# wtv_sch.net
KiCad netlist of a schematic drawn in EAGLE
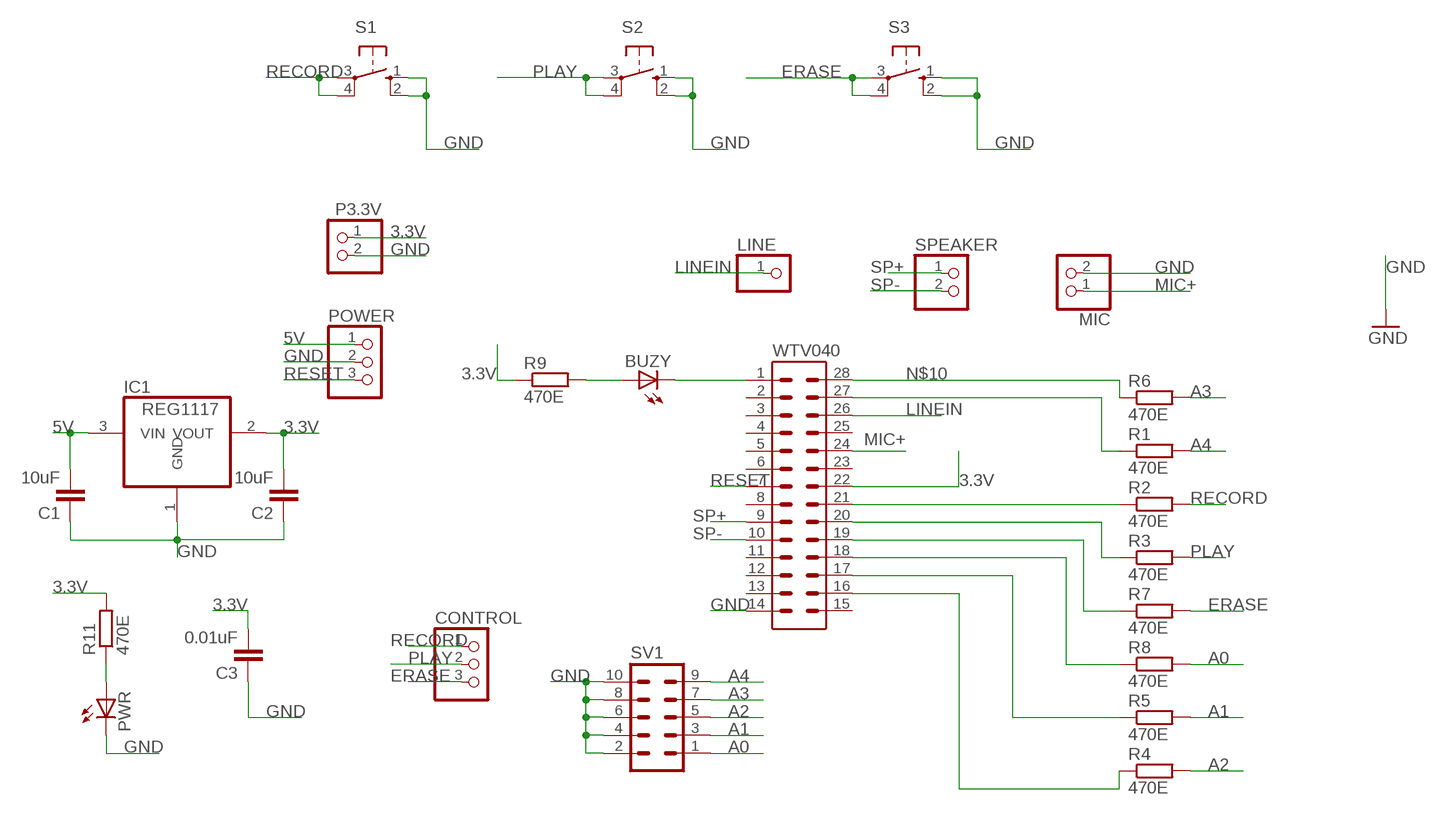
[diagram p0: schematic, sheet 1]

(export (version "E")
  (design (tool "Eeschema 10.0.6"))
  (components
    (comp (ref "BUZY")
      (value "LEDSML0805")
      (footprint "eagle-import:SML0805")
      (libsource (lib "eagle-import") (part "LEDSML0805"))
    )
    (comp (ref "C1")
      (value "10uF")
      (footprint "eagle-import:C0805")
      (libsource (lib "eagle-import") (part "C-EUC0805"))
    )
    (comp (ref "C2")
      (value "10uF")
      (footprint "eagle-import:C0805")
      (libsource (lib "eagle-import") (part "C-EUC0805"))
    )
    (comp (ref "C3")
      (value "0.01uF")
      (footprint "eagle-import:C0805")
      (libsource (lib "eagle-import") (part "C-EUC0805"))
    )
    (comp (ref "CONTROL")
      (value "PINHD-1X3")
      (footprint "eagle-import:1X03")
      (libsource (lib "eagle-import") (part "PINHD-1X3"))
    )
    (comp (ref "IC1")
      (value "REG1117")
      (footprint "eagle-import:SOT223")
      (libsource (lib "eagle-import") (part "REG1117"))
    )
    (comp (ref "LINE")
      (value "PINHD-1X1")
      (footprint "eagle-import:1X01")
      (libsource (lib "eagle-import") (part "PINHD-1X1"))
    )
    (comp (ref "MIC")
      (value "PINHD-1X2")
      (footprint "eagle-import:1X02")
      (libsource (lib "eagle-import") (part "PINHD-1X2"))
    )
    (comp (ref "P3.3V")
      (value "PINHD-1X2")
      (footprint "eagle-import:1X02")
      (libsource (lib "eagle-import") (part "PINHD-1X2"))
    )
    (comp (ref "POWER")
      (value "PINHD-1X3")
      (footprint "eagle-import:1X03")
      (libsource (lib "eagle-import") (part "PINHD-1X3"))
    )
    (comp (ref "PWR")
      (value "LEDSML0805")
      (footprint "eagle-import:SML0805")
      (libsource (lib "eagle-import") (part "LEDSML0805"))
    )
    (comp (ref "R1")
      (value "470E")
      (footprint "eagle-import:R0805")
      (libsource (lib "eagle-import") (part "R-EU_R0805"))
    )
    (comp (ref "R2")
      (value "470E")
      (footprint "eagle-import:R0805")
      (libsource (lib "eagle-import") (part "R-EU_R0805"))
    )
    (comp (ref "R3")
      (value "470E")
      (footprint "eagle-import:R0805")
      (libsource (lib "eagle-import") (part "R-EU_R0805"))
    )
    (comp (ref "R4")
      (value "470E")
      (footprint "eagle-import:R0805")
      (libsource (lib "eagle-import") (part "R-EU_R0805"))
    )
    (comp (ref "R5")
      (value "470E")
      (footprint "eagle-import:R0805")
      (libsource (lib "eagle-import") (part "R-EU_R0805"))
    )
    (comp (ref "R6")
      (value "470E")
      (footprint "eagle-import:R0805")
      (libsource (lib "eagle-import") (part "R-EU_R0805"))
    )
    (comp (ref "R7")
      (value "470E")
      (footprint "eagle-import:R0805")
      (libsource (lib "eagle-import") (part "R-EU_R0805"))
    )
    (comp (ref "R8")
      (value "470E")
      (footprint "eagle-import:R0805")
      (libsource (lib "eagle-import") (part "R-EU_R0805"))
    )
    (comp (ref "R9")
      (value "470E")
      (footprint "eagle-import:R0805")
      (libsource (lib "eagle-import") (part "R-EU_R0805"))
    )
    (comp (ref "R11")
      (value "470E")
      (footprint "eagle-import:R0805")
      (libsource (lib "eagle-import") (part "R-EU_R0805"))
    )
    (comp (ref "S1")
      (value "10-XX")
      (footprint "eagle-import:B3F-10XX")
      (fields (field (name "MPN") "B3F-1000"))
      (libsource (lib "eagle-import") (part "10-XX"))
    )
    (comp (ref "S2")
      (value "10-XX")
      (footprint "eagle-import:B3F-10XX")
      (fields (field (name "MPN") "B3F-1000"))
      (libsource (lib "eagle-import") (part "10-XX"))
    )
    (comp (ref "S3")
      (value "10-XX")
      (footprint "eagle-import:B3F-10XX")
      (fields (field (name "MPN") "B3F-1000"))
      (libsource (lib "eagle-import") (part "10-XX"))
    )
    (comp (ref "SPEAKER")
      (value "PINHD-1X2")
      (footprint "eagle-import:1X02")
      (libsource (lib "eagle-import") (part "PINHD-1X2"))
    )
    (comp (ref "SV1")
      (value "MA05-2")
      (footprint "eagle-import:MA05-2")
      (libsource (lib "eagle-import") (part "MA05-2"))
    )
    (comp (ref "WTV040")
      (value "IC28P")
      (footprint "eagle-import:IC28P")
      (libsource (lib "eagle-import") (part "IC28P"))
    )
  )
  (nets
    (net (code "1") (name "/3.3V") (class "Default")
      (node (ref "C2") (pin "2") (pinfunction "2_2") (pintype "passive"))
      (node (ref "C3") (pin "2") (pinfunction "2_2") (pintype "passive"))
      (node (ref "IC1") (pin "2") (pinfunction "VOUT_2") (pintype "output"))
      (node (ref "P3.3V") (pin "1") (pinfunction "1_1") (pintype "passive"))
      (node (ref "R11") (pin "2") (pinfunction "2_2") (pintype "passive"))
      (node (ref "R9") (pin "1") (pinfunction "1_1") (pintype "passive"))
      (node (ref "WTV040") (pin "22") (pinfunction "22_22") (pintype "passive"))
    )
    (net (code "2") (name "/5V") (class "Default")
      (node (ref "C1") (pin "2") (pinfunction "2_2") (pintype "passive"))
      (node (ref "IC1") (pin "3") (pinfunction "VIN_3") (pintype "input"))
      (node (ref "POWER") (pin "1") (pinfunction "1_1") (pintype "passive"))
    )
    (net (code "3") (name "/A0") (class "Default")
      (node (ref "R8") (pin "2") (pinfunction "2_2") (pintype "passive"))
      (node (ref "SV1") (pin "1") (pinfunction "1_1") (pintype "passive"))
    )
    (net (code "4") (name "/A1") (class "Default")
      (node (ref "R5") (pin "2") (pinfunction "2_2") (pintype "passive"))
      (node (ref "SV1") (pin "3") (pinfunction "3_3") (pintype "passive"))
    )
    (net (code "5") (name "/A2") (class "Default")
      (node (ref "R4") (pin "2") (pinfunction "2_2") (pintype "passive"))
      (node (ref "SV1") (pin "5") (pinfunction "5_5") (pintype "passive"))
    )
    (net (code "6") (name "/A3") (class "Default")
      (node (ref "R6") (pin "2") (pinfunction "2_2") (pintype "passive"))
      (node (ref "SV1") (pin "7") (pinfunction "7_7") (pintype "passive"))
    )
    (net (code "7") (name "/A4") (class "Default")
      (node (ref "R1") (pin "2") (pinfunction "2_2") (pintype "passive"))
      (node (ref "SV1") (pin "9") (pinfunction "9_9") (pintype "passive"))
    )
    (net (code "8") (name "/ERASE") (class "Default")
      (node (ref "CONTROL") (pin "3") (pinfunction "3_3") (pintype "passive"))
      (node (ref "R7") (pin "2") (pinfunction "2_2") (pintype "passive"))
      (node (ref "S3") (pin "3") (pinfunction "P_3") (pintype "passive"))
      (node (ref "S3") (pin "4") (pinfunction "P1_4") (pintype "passive"))
    )
    (net (code "9") (name "/LINEIN") (class "Default")
      (node (ref "LINE") (pin "1") (pinfunction "1_1") (pintype "passive"))
      (node (ref "WTV040") (pin "26") (pinfunction "26_26") (pintype "passive"))
    )
    (net (code "10") (name "/MIC+") (class "Default")
      (node (ref "MIC") (pin "1") (pinfunction "1_1") (pintype "passive"))
      (node (ref "WTV040") (pin "24") (pinfunction "24_24") (pintype "passive"))
    )
    (net (code "11") (name "/N$10") (class "Default")
      (node (ref "R6") (pin "1") (pinfunction "1_1") (pintype "passive"))
      (node (ref "WTV040") (pin "28") (pinfunction "28_28") (pintype "passive"))
    )
    (net (code "12") (name "/PLAY") (class "Default")
      (node (ref "CONTROL") (pin "2") (pinfunction "2_2") (pintype "passive"))
      (node (ref "R3") (pin "2") (pinfunction "2_2") (pintype "passive"))
      (node (ref "S2") (pin "3") (pinfunction "P_3") (pintype "passive"))
      (node (ref "S2") (pin "4") (pinfunction "P1_4") (pintype "passive"))
    )
    (net (code "13") (name "/RECORD") (class "Default")
      (node (ref "CONTROL") (pin "1") (pinfunction "1_1") (pintype "passive"))
      (node (ref "R2") (pin "2") (pinfunction "2_2") (pintype "passive"))
      (node (ref "S1") (pin "3") (pinfunction "P_3") (pintype "passive"))
      (node (ref "S1") (pin "4") (pinfunction "P1_4") (pintype "passive"))
    )
    (net (code "14") (name "/RESET") (class "Default")
      (node (ref "POWER") (pin "3") (pinfunction "3_3") (pintype "passive"))
      (node (ref "WTV040") (pin "7") (pinfunction "7_7") (pintype "passive"))
    )
    (net (code "15") (name "/SP+") (class "Default")
      (node (ref "SPEAKER") (pin "1") (pinfunction "1_1") (pintype "passive"))
      (node (ref "WTV040") (pin "9") (pinfunction "9_9") (pintype "passive"))
    )
    (net (code "16") (name "/SP-") (class "Default")
      (node (ref "SPEAKER") (pin "2") (pinfunction "2_2") (pintype "passive"))
      (node (ref "WTV040") (pin "10") (pinfunction "10_10") (pintype "passive"))
    )
    (net (code "17") (name "GND") (class "Default")
      (node (ref "C1") (pin "1") (pinfunction "1_1") (pintype "passive"))
      (node (ref "C2") (pin "1") (pinfunction "1_1") (pintype "passive"))
      (node (ref "C3") (pin "1") (pinfunction "1_1") (pintype "passive"))
      (node (ref "IC1") (pin "1") (pinfunction "GND_1") (pintype "power_in"))
      (node (ref "MIC") (pin "2") (pinfunction "2_2") (pintype "passive"))
      (node (ref "P3.3V") (pin "2") (pinfunction "2_2") (pintype "passive"))
      (node (ref "POWER") (pin "2") (pinfunction "2_2") (pintype "passive"))
      (node (ref "PWR") (pin "C") (pinfunction "C_C") (pintype "passive"))
      (node (ref "S1") (pin "1") (pinfunction "S_1") (pintype "passive"))
      (node (ref "S1") (pin "2") (pinfunction "S1_2") (pintype "passive"))
      (node (ref "S2") (pin "1") (pinfunction "S_1") (pintype "passive"))
      (node (ref "S2") (pin "2") (pinfunction "S1_2") (pintype "passive"))
      (node (ref "S3") (pin "1") (pinfunction "S_1") (pintype "passive"))
      (node (ref "S3") (pin "2") (pinfunction "S1_2") (pintype "passive"))
      (node (ref "SV1") (pin "10") (pinfunction "10_10") (pintype "passive"))
      (node (ref "SV1") (pin "2") (pinfunction "2_2") (pintype "passive"))
      (node (ref "SV1") (pin "4") (pinfunction "4_4") (pintype "passive"))
      (node (ref "SV1") (pin "6") (pinfunction "6_6") (pintype "passive"))
      (node (ref "SV1") (pin "8") (pinfunction "8_8") (pintype "passive"))
      (node (ref "WTV040") (pin "14") (pinfunction "14_14") (pintype "passive"))
    )
    (net (code "18") (name "Net-(BUZY-PadA)") (class "Default")
      (node (ref "BUZY") (pin "A") (pinfunction "A_A") (pintype "passive"))
      (node (ref "R9") (pin "2") (pinfunction "2_2") (pintype "passive"))
    )
    (net (code "19") (name "Net-(BUZY-PadC)") (class "Default")
      (node (ref "BUZY") (pin "C") (pinfunction "C_C") (pintype "passive"))
      (node (ref "WTV040") (pin "1") (pinfunction "1_1") (pintype "passive"))
    )
    (net (code "20") (name "Net-(PWR-PadA)") (class "Default")
      (node (ref "PWR") (pin "A") (pinfunction "A_A") (pintype "passive"))
      (node (ref "R11") (pin "1") (pinfunction "1_1") (pintype "passive"))
    )
    (net (code "21") (name "Net-(R1-Pad1)") (class "Default")
      (node (ref "R1") (pin "1") (pinfunction "1_1") (pintype "passive"))
      (node (ref "WTV040") (pin "27") (pinfunction "27_27") (pintype "passive"))
    )
    (net (code "22") (name "Net-(R2-Pad1)") (class "Default")
      (node (ref "R2") (pin "1") (pinfunction "1_1") (pintype "passive"))
      (node (ref "WTV040") (pin "21") (pinfunction "21_21") (pintype "passive"))
    )
    (net (code "23") (name "Net-(R3-Pad1)") (class "Default")
      (node (ref "R3") (pin "1") (pinfunction "1_1") (pintype "passive"))
      (node (ref "WTV040") (pin "20") (pinfunction "20_20") (pintype "passive"))
    )
    (net (code "24") (name "Net-(R4-Pad1)") (class "Default")
      (node (ref "R4") (pin "1") (pinfunction "1_1") (pintype "passive"))
      (node (ref "WTV040") (pin "16") (pinfunction "16_16") (pintype "passive"))
    )
    (net (code "25") (name "Net-(R5-Pad1)") (class "Default")
      (node (ref "R5") (pin "1") (pinfunction "1_1") (pintype "passive"))
      (node (ref "WTV040") (pin "17") (pinfunction "17_17") (pintype "passive"))
    )
    (net (code "26") (name "Net-(R7-Pad1)") (class "Default")
      (node (ref "R7") (pin "1") (pinfunction "1_1") (pintype "passive"))
      (node (ref "WTV040") (pin "19") (pinfunction "19_19") (pintype "passive"))
    )
    (net (code "27") (name "Net-(R8-Pad1)") (class "Default")
      (node (ref "R8") (pin "1") (pinfunction "1_1") (pintype "passive"))
      (node (ref "WTV040") (pin "18") (pinfunction "18_18") (pintype "passive"))
    )
    (net (code "28") (name "unconnected-(WTV040-Pad2)") (class "Default")
      (node (ref "WTV040") (pin "2") (pinfunction "2_2") (pintype "passive"))
    )
    (net (code "29") (name "unconnected-(WTV040-Pad3)") (class "Default")
      (node (ref "WTV040") (pin "3") (pinfunction "3_3") (pintype "passive"))
    )
    (net (code "30") (name "unconnected-(WTV040-Pad4)") (class "Default")
      (node (ref "WTV040") (pin "4") (pinfunction "4_4") (pintype "passive"))
    )
    (net (code "31") (name "unconnected-(WTV040-Pad5)") (class "Default")
      (node (ref "WTV040") (pin "5") (pinfunction "5_5") (pintype "passive"))
    )
    (net (code "32") (name "unconnected-(WTV040-Pad6)") (class "Default")
      (node (ref "WTV040") (pin "6") (pinfunction "6_6") (pintype "passive"))
    )
    (net (code "33") (name "unconnected-(WTV040-Pad8)") (class "Default")
      (node (ref "WTV040") (pin "8") (pinfunction "8_8") (pintype "passive"))
    )
    (net (code "34") (name "unconnected-(WTV040-Pad11)") (class "Default")
      (node (ref "WTV040") (pin "11") (pinfunction "11_11") (pintype "passive"))
    )
    (net (code "35") (name "unconnected-(WTV040-Pad12)") (class "Default")
      (node (ref "WTV040") (pin "12") (pinfunction "12_12") (pintype "passive"))
    )
    (net (code "36") (name "unconnected-(WTV040-Pad13)") (class "Default")
      (node (ref "WTV040") (pin "13") (pinfunction "13_13") (pintype "passive"))
    )
    (net (code "37") (name "unconnected-(WTV040-Pad15)") (class "Default")
      (node (ref "WTV040") (pin "15") (pinfunction "15_15") (pintype "passive"))
    )
    (net (code "38") (name "unconnected-(WTV040-Pad23)") (class "Default")
      (node (ref "WTV040") (pin "23") (pinfunction "23_23") (pintype "passive"))
    )
    (net (code "39") (name "unconnected-(WTV040-Pad25)") (class "Default")
      (node (ref "WTV040") (pin "25") (pinfunction "25_25") (pintype "passive"))
    )
  )
)
